# SparkWireInterface.net
KiCad netlist of a schematic drawn in EAGLE
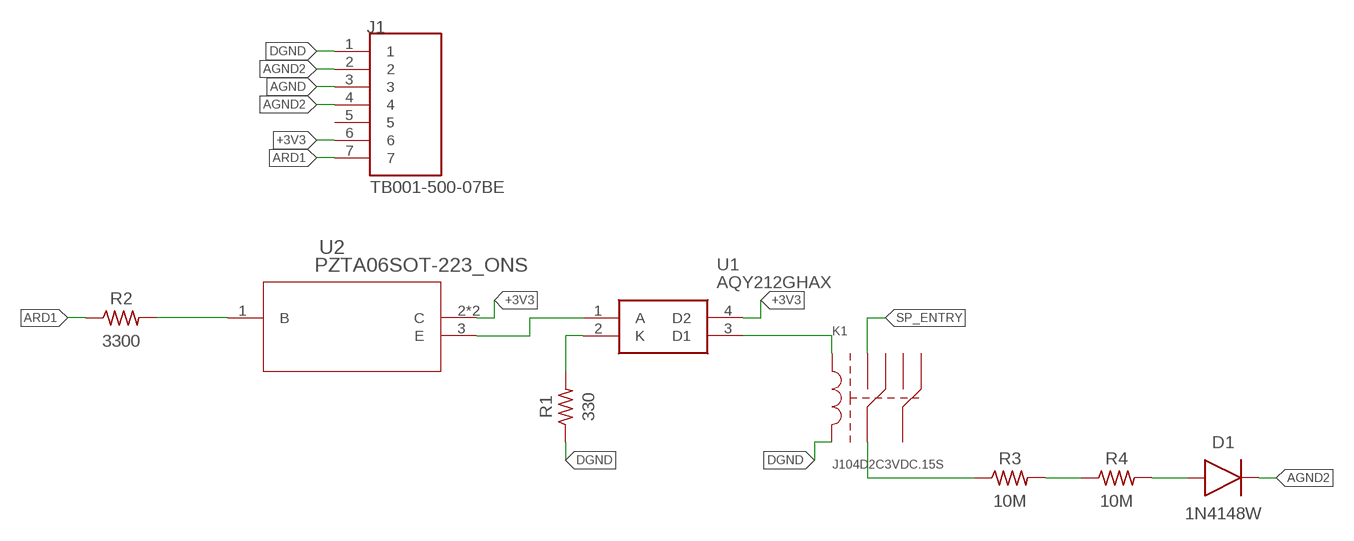
[diagram p0: schematic, sheet 1]

(export (version "E")
  (design (tool "Eeschema 10.0.6"))
  (components
    (comp (ref "D1")
      (value "1N4148W")
      (footprint "eagle-import:SOD3715X135")
      (fields (field (name "MANUFACTURER") "Diodes Incorporated"))
      (libsource (lib "eagle-import") (part "DIODE__SOD123G1N4148W-7-F"))
    )
    (comp (ref "J1")
      (value "TB001-500-07BE")
      (footprint "eagle-import:CUI_TB001-500-07BE")
      (fields (field (name "MANUFACTURER") "CUI"))
      (libsource (lib "eagle-import") (part "TB001-500-07BE"))
    )
    (comp (ref "K1")
      (value "J104D2C3VDC.15S")
      (footprint "eagle-import:J104D2C3VDC.15S")
      (libsource (lib "eagle-import") (part "J104D2C3VDC.15S"))
    )
    (comp (ref "R1")
      (value "330")
      (footprint "eagle-import:RESC1608X60")
      (libsource (lib "eagle-import") (part "R-USCHIP-0603(1608-METRIC)_"))
    )
    (comp (ref "R2")
      (value "3300")
      (footprint "eagle-import:RESC1608X60")
      (libsource (lib "eagle-import") (part "R-USCHIP-0603(1608-METRIC)_"))
    )
    (comp (ref "R3")
      (value "10M")
      (footprint "eagle-import:RESC6332X71")
      (libsource (lib "eagle-import") (part "R-USCHIP-2512(6332-METRIC)_"))
    )
    (comp (ref "R4")
      (value "10M")
      (footprint "eagle-import:RESC6332X71")
      (libsource (lib "eagle-import") (part "R-USCHIP-2512(6332-METRIC)_"))
    )
    (comp (ref "U1")
      (value "AQY212GHAX")
      (footprint "eagle-import:SOP254P962X315-4N")
      (fields (field (name "MOUSER_PART_NUMBER") "667-AQY212GHAX"))
      (libsource (lib "eagle-import") (part "AQY212GHAX"))
    )
    (comp (ref "U2")
      (value "PZTA06SOT-223_ONS")
      (footprint "eagle-import:SOT-223_ONS")
      (fields
        (field (name "MANUFACTURER_PART_NUMBER") "PZTA06")
        (field (name "COPYRIGHT") "Copyright (C) 2022 Ultra Librarian. All rights reserved.")
      )
      (libsource (lib "eagle-import") (part "PZTA06SOT-223_ONS"))
    )
  )
  (nets
    (net (code "1") (name "+3V3") (class "Default")
      (node (ref "J1") (pin "6") (pinfunction "6_6") (pintype "passive"))
      (node (ref "U1") (pin "4") (pinfunction "D2_4") (pintype "bidirectional"))
      (node (ref "U2") (pin "2") (pinfunction "C_2") (pintype "passive"))
      (node (ref "U2") (pin "4") (pinfunction "C_4") (pintype "passive"))
    )
    (net (code "2") (name "AGND") (class "Default")
      (node (ref "J1") (pin "3") (pinfunction "3_3") (pintype "passive"))
    )
    (net (code "3") (name "AGND2") (class "Default")
      (node (ref "D1") (pin "1") (pinfunction "C_1") (pintype "passive"))
      (node (ref "J1") (pin "2") (pinfunction "2_2") (pintype "passive"))
      (node (ref "J1") (pin "4") (pinfunction "4_4") (pintype "passive"))
    )
    (net (code "4") (name "ARD1") (class "Default")
      (node (ref "J1") (pin "7") (pinfunction "7_7") (pintype "passive"))
      (node (ref "R2") (pin "1") (pinfunction "1_1") (pintype "passive"))
    )
    (net (code "5") (name "DGND") (class "Default")
      (node (ref "J1") (pin "1") (pinfunction "1_1") (pintype "passive"))
      (node (ref "K1") (pin "1") (pinfunction "LA_1") (pintype "bidirectional"))
      (node (ref "R1") (pin "1") (pinfunction "1_1") (pintype "passive"))
    )
    (net (code "6") (name "Net-(D1-A)") (class "Default")
      (node (ref "D1") (pin "2") (pinfunction "A_2") (pintype "passive"))
      (node (ref "R4") (pin "2") (pinfunction "2_2") (pintype "passive"))
    )
    (net (code "7") (name "Net-(K1-C1)") (class "Default")
      (node (ref "K1") (pin "3") (pinfunction "C1_3") (pintype "bidirectional"))
      (node (ref "R3") (pin "1") (pinfunction "1_1") (pintype "passive"))
    )
    (net (code "8") (name "Net-(K1-LB)") (class "Default")
      (node (ref "K1") (pin "2") (pinfunction "LB_2") (pintype "bidirectional"))
      (node (ref "U1") (pin "3") (pinfunction "D1_3") (pintype "bidirectional"))
    )
    (net (code "9") (name "Net-(R3-Pad2)") (class "Default")
      (node (ref "R3") (pin "2") (pinfunction "2_2") (pintype "passive"))
      (node (ref "R4") (pin "1") (pinfunction "1_1") (pintype "passive"))
    )
    (net (code "10") (name "Net-(U1-A)") (class "Default")
      (node (ref "U1") (pin "1") (pinfunction "A_1") (pintype "bidirectional"))
      (node (ref "U2") (pin "3") (pinfunction "E_3") (pintype "passive"))
    )
    (net (code "11") (name "Net-(U1-K)") (class "Default")
      (node (ref "R1") (pin "2") (pinfunction "2_2") (pintype "passive"))
      (node (ref "U1") (pin "2") (pinfunction "K_2") (pintype "bidirectional"))
    )
    (net (code "12") (name "Net-(U2-B)") (class "Default")
      (node (ref "R2") (pin "2") (pinfunction "2_2") (pintype "passive"))
      (node (ref "U2") (pin "1") (pinfunction "B_1") (pintype "passive"))
    )
    (net (code "13") (name "SP_ENTRY") (class "Default")
      (node (ref "K1") (pin "7") (pinfunction "NO1_7") (pintype "bidirectional"))
    )
    (net (code "14") (name "unconnected-(J1-Pad5)") (class "Default")
      (node (ref "J1") (pin "5") (pinfunction "5_5") (pintype "passive"))
    )
    (net (code "15") (name "unconnected-(K1-C2-Pad4)") (class "Default")
      (node (ref "K1") (pin "4") (pinfunction "C2_4") (pintype "bidirectional"))
    )
    (net (code "16") (name "unconnected-(K1-NC1-Pad5)") (class "Default")
      (node (ref "K1") (pin "5") (pinfunction "NC1_5") (pintype "bidirectional"))
    )
    (net (code "17") (name "unconnected-(K1-NC2-Pad6)") (class "Default")
      (node (ref "K1") (pin "6") (pinfunction "NC2_6") (pintype "bidirectional"))
    )
    (net (code "18") (name "unconnected-(K1-NO2-Pad8)") (class "Default")
      (node (ref "K1") (pin "8") (pinfunction "NO2_8") (pintype "bidirectional"))
    )
  )
)
